# lcd_keyb.net
KiCad netlist of a schematic drawn in Altium Designer
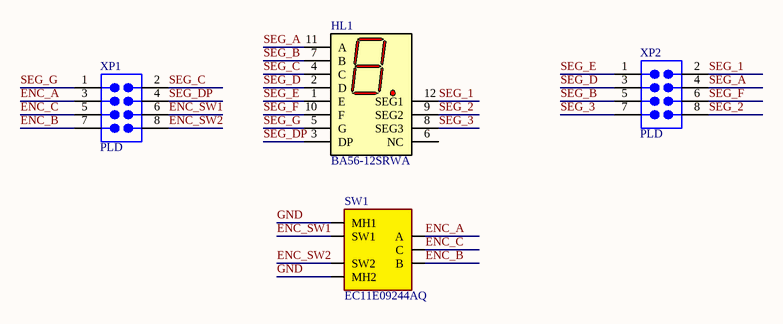
[diagram p0: lcd_keyb.SchDoc]

(export (version "E")
  (design (tool "Eeschema 10.0.6"))
  (components
    (comp (ref "HL1")
      (value "BA56-12SRWA")
      (footprint "BX56-12")
      (libsource (lib "Optoelectronics") (part "BX56-12"))
    )
    (comp (ref "SW1")
      (value "EC11E09244AQ")
      (footprint "EC11E09244AQ")
      (libsource (lib "Button") (part "RotaryEncoder"))
    )
    (comp (ref "XP1")
      (value "PLD")
      (footprint "PLD-08R")
      (fields (field (name "PART NUMBER") "PLD-08R"))
      (libsource (lib "Connector") (part "CN_08P_2W"))
    )
    (comp (ref "XP2")
      (value "PLD")
      (footprint "PLD-08R")
      (fields (field (name "PART NUMBER") "PLD-08R"))
      (libsource (lib "Connector") (part "CN_08P_2W"))
    )
  )
  (nets
    (net (code "1") (name "/ENC_A") (class "Default")
      (node (ref "SW1") (pin "A") (pinfunction "A_A") (pintype "passive"))
      (node (ref "XP1") (pin "3") (pinfunction "3_3") (pintype "passive"))
    )
    (net (code "2") (name "/ENC_B") (class "Default")
      (node (ref "SW1") (pin "B") (pinfunction "B_B") (pintype "passive"))
      (node (ref "XP1") (pin "7") (pinfunction "7_7") (pintype "passive"))
    )
    (net (code "3") (name "/ENC_C") (class "Default")
      (node (ref "SW1") (pin "C") (pinfunction "C_C") (pintype "passive"))
      (node (ref "XP1") (pin "5") (pinfunction "5_5") (pintype "passive"))
    )
    (net (code "4") (name "/ENC_SW1") (class "Default")
      (node (ref "SW1") (pin "SW1") (pinfunction "SW1_SW1") (pintype "passive"))
      (node (ref "XP1") (pin "6") (pinfunction "6_6") (pintype "passive"))
    )
    (net (code "5") (name "/ENC_SW2") (class "Default")
      (node (ref "SW1") (pin "SW2") (pinfunction "SW2_SW2") (pintype "passive"))
      (node (ref "XP1") (pin "8") (pinfunction "8_8") (pintype "passive"))
    )
    (net (code "6") (name "/GND") (class "Default")
      (node (ref "SW1") (pin "MH1") (pinfunction "MH1_MH1") (pintype "passive"))
      (node (ref "SW1") (pin "MH2") (pinfunction "MH2_MH2") (pintype "passive"))
    )
    (net (code "7") (name "/SEG_1") (class "Default")
      (node (ref "HL1") (pin "12") (pinfunction "SEG1_12") (pintype "passive"))
      (node (ref "XP2") (pin "2") (pinfunction "2_2") (pintype "passive"))
    )
    (net (code "8") (name "/SEG_2") (class "Default")
      (node (ref "HL1") (pin "9") (pinfunction "SEG2_9") (pintype "passive"))
      (node (ref "XP2") (pin "8") (pinfunction "8_8") (pintype "passive"))
    )
    (net (code "9") (name "/SEG_3") (class "Default")
      (node (ref "HL1") (pin "8") (pinfunction "SEG3_8") (pintype "passive"))
      (node (ref "XP2") (pin "7") (pinfunction "7_7") (pintype "passive"))
    )
    (net (code "10") (name "/SEG_A") (class "Default")
      (node (ref "HL1") (pin "11") (pinfunction "A_11") (pintype "passive"))
      (node (ref "XP2") (pin "4") (pinfunction "4_4") (pintype "passive"))
    )
    (net (code "11") (name "/SEG_B") (class "Default")
      (node (ref "HL1") (pin "7") (pinfunction "B_7") (pintype "passive"))
      (node (ref "XP2") (pin "5") (pinfunction "5_5") (pintype "passive"))
    )
    (net (code "12") (name "/SEG_C") (class "Default")
      (node (ref "HL1") (pin "4") (pinfunction "C_4") (pintype "passive"))
      (node (ref "XP1") (pin "2") (pinfunction "2_2") (pintype "passive"))
    )
    (net (code "13") (name "/SEG_D") (class "Default")
      (node (ref "HL1") (pin "2") (pinfunction "D_2") (pintype "passive"))
      (node (ref "XP2") (pin "3") (pinfunction "3_3") (pintype "passive"))
    )
    (net (code "14") (name "/SEG_DP") (class "Default")
      (node (ref "HL1") (pin "3") (pinfunction "DP_3") (pintype "passive"))
      (node (ref "XP1") (pin "4") (pinfunction "4_4") (pintype "passive"))
    )
    (net (code "15") (name "/SEG_E") (class "Default")
      (node (ref "HL1") (pin "1") (pinfunction "E_1") (pintype "passive"))
      (node (ref "XP2") (pin "1") (pinfunction "1_1") (pintype "passive"))
    )
    (net (code "16") (name "/SEG_F") (class "Default")
      (node (ref "HL1") (pin "10") (pinfunction "F_10") (pintype "passive"))
      (node (ref "XP2") (pin "6") (pinfunction "6_6") (pintype "passive"))
    )
    (net (code "17") (name "/SEG_G") (class "Default")
      (node (ref "HL1") (pin "5") (pinfunction "G_5") (pintype "passive"))
      (node (ref "XP1") (pin "1") (pinfunction "1_1") (pintype "passive"))
    )
    (net (code "18") (name "unconnected-(HL1-NC-Pad6)") (class "Default")
      (node (ref "HL1") (pin "6") (pinfunction "NC_6") (pintype "passive"))
    )
  )
)
